# MoogFilter_DIL.net
KiCad netlist of a schematic drawn in EAGLE
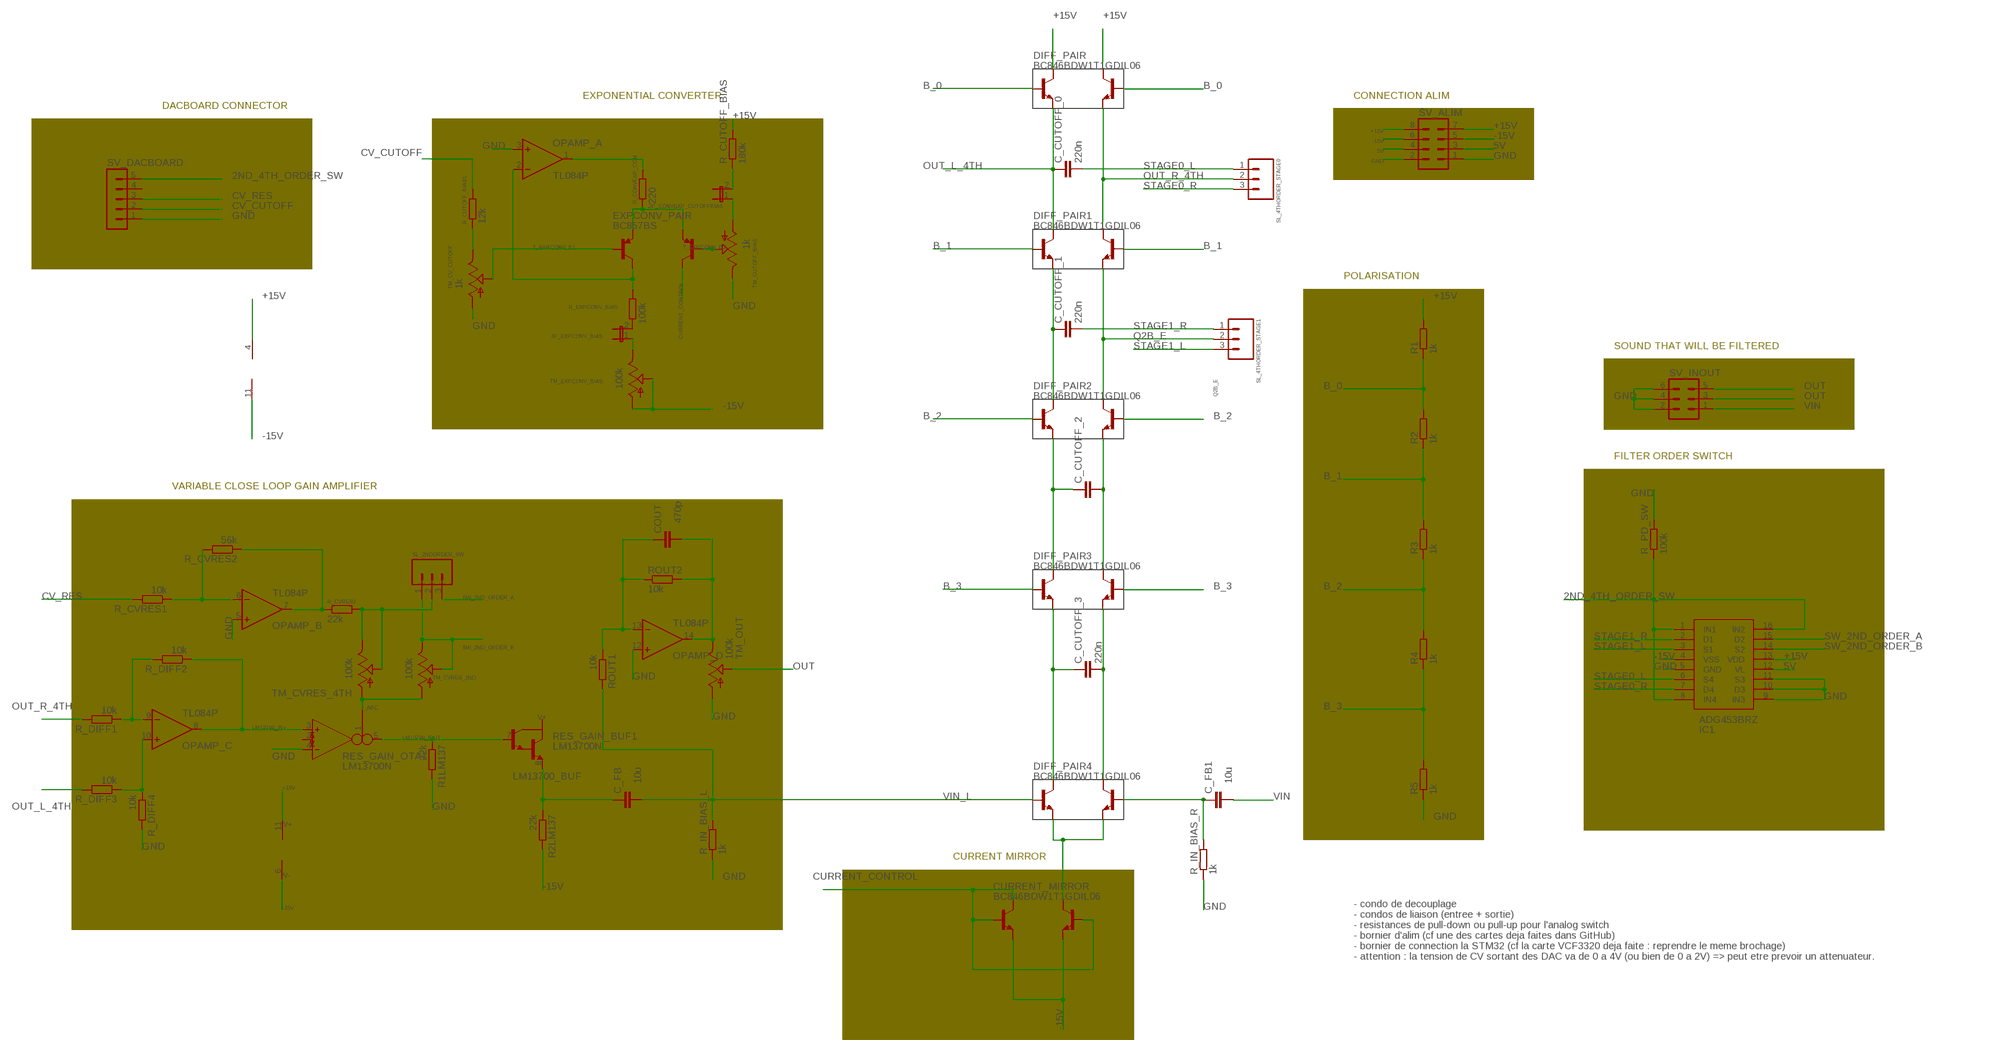
[diagram p0: schematic, sheet 1]

(export (version "E")
  (design (tool "Eeschema 10.0.6"))
  (components
    (comp (ref "COUT")
      (value "470p")
      (footprint "eagle-import:C5B2.5")
      (libsource (lib "eagle-import") (part "C5/2.5"))
    )
    (comp (ref "CURRENT_MIRROR")
      (value "BC846BDW1T1GDIL06")
      (footprint "eagle-import:DIL06")
      (libsource (lib "eagle-import") (part "BC846BDW1T1GDIL06"))
    )
    (comp (ref "C_CUTOFF_0")
      (value "220n")
      (footprint "eagle-import:C5B3")
      (libsource (lib "eagle-import") (part "C5/3"))
    )
    (comp (ref "C_CUTOFF_1")
      (value "220n")
      (footprint "eagle-import:C5B2.5")
      (libsource (lib "eagle-import") (part "C5/2.5"))
    )
    (comp (ref "C_CUTOFF_2")
      (value "220n")
      (footprint "eagle-import:C5B2.5")
      (libsource (lib "eagle-import") (part "C5/2.5"))
    )
    (comp (ref "C_CUTOFF_3")
      (value "220n")
      (footprint "eagle-import:C5B2.5")
      (libsource (lib "eagle-import") (part "C5/2.5"))
    )
    (comp (ref "C_FB")
      (value "10u")
      (footprint "eagle-import:C5B2.5")
      (libsource (lib "eagle-import") (part "C5/2.5"))
    )
    (comp (ref "C_FB1")
      (value "10u")
      (footprint "eagle-import:C5B2.5")
      (libsource (lib "eagle-import") (part "C5/2.5"))
    )
    (comp (ref "DIFF_PAIR")
      (value "BC846BDW1T1GDIL06")
      (footprint "eagle-import:DIL06")
      (libsource (lib "eagle-import") (part "BC846BDW1T1GDIL06"))
    )
    (comp (ref "DIFF_PAIR1")
      (value "BC846BDW1T1GDIL06")
      (footprint "eagle-import:DIL06")
      (libsource (lib "eagle-import") (part "BC846BDW1T1GDIL06"))
    )
    (comp (ref "DIFF_PAIR2")
      (value "BC846BDW1T1GDIL06")
      (footprint "eagle-import:DIL06")
      (libsource (lib "eagle-import") (part "BC846BDW1T1GDIL06"))
    )
    (comp (ref "DIFF_PAIR3")
      (value "BC846BDW1T1GDIL06")
      (footprint "eagle-import:DIL06")
      (libsource (lib "eagle-import") (part "BC846BDW1T1GDIL06"))
    )
    (comp (ref "DIFF_PAIR4")
      (value "BC846BDW1T1GDIL06")
      (footprint "eagle-import:DIL06")
      (libsource (lib "eagle-import") (part "BC846BDW1T1GDIL06"))
    )
    (comp (ref "EXPCONV_PAIR")
      (value "BC857BS")
      (footprint "eagle-import:DIL06")
      (libsource (lib "eagle-import") (part "BC857BS"))
    )
    (comp (ref "IC1")
      (value "ADG453BRZ")
      (footprint "eagle-import:SOIC127P600X175-16N")
      (fields (field (name "MOUSER_PART_NUMBER") "584-ADG453BRZ") (field (name "RS_PART_NUMBER") "0412539P"))
      (libsource (lib "eagle-import") (part "ADG453BRZ"))
    )
    (comp (ref "JP_CONVEXP_CUTOFFBIAS")
      (value "JP1E")
      (footprint "eagle-import:JP1")
      (libsource (lib "eagle-import") (part "JP1E"))
    )
    (comp (ref "JP_EXPCONV_BIAS")
      (value "JP1E")
      (footprint "eagle-import:JP1")
      (libsource (lib "eagle-import") (part "JP1E"))
    )
    (comp (ref "OPAMP_")
      (value "TL084P")
      (footprint "eagle-import:DIL14")
      (libsource (lib "eagle-import") (part "TL084P"))
    )
    (comp (ref "R1")
      (value "1k")
      (footprint "eagle-import:0204_7")
      (libsource (lib "eagle-import") (part "R-EU_0204/7"))
    )
    (comp (ref "R1LM137")
      (value "22k")
      (footprint "eagle-import:0204_7")
      (libsource (lib "eagle-import") (part "R-EU_0204/7"))
    )
    (comp (ref "R2")
      (value "1k")
      (footprint "eagle-import:0204_7")
      (libsource (lib "eagle-import") (part "R-EU_0204/7"))
    )
    (comp (ref "R2LM137")
      (value "22k")
      (footprint "eagle-import:0204_7")
      (libsource (lib "eagle-import") (part "R-EU_0204/7"))
    )
    (comp (ref "R3")
      (value "1k")
      (footprint "eagle-import:0204_7")
      (libsource (lib "eagle-import") (part "R-EU_0204/7"))
    )
    (comp (ref "R4")
      (value "1k")
      (footprint "eagle-import:0204_7")
      (libsource (lib "eagle-import") (part "R-EU_0204/7"))
    )
    (comp (ref "R5")
      (value "1k")
      (footprint "eagle-import:0204_7")
      (libsource (lib "eagle-import") (part "R-EU_0204/7"))
    )
    (comp (ref "RES_GAIN_")
      (value "LM13700N")
      (footprint "eagle-import:DIL16")
      (libsource (lib "eagle-import") (part "LM13700N"))
    )
    (comp (ref "ROUT1")
      (value "10k")
      (footprint "eagle-import:0204_7")
      (libsource (lib "eagle-import") (part "R-EU_0204/7"))
    )
    (comp (ref "ROUT2")
      (value "10k")
      (footprint "eagle-import:0204_7")
      (libsource (lib "eagle-import") (part "R-EU_0204/7"))
    )
    (comp (ref "R_CONVEXP_COM")
      (value "220")
      (footprint "eagle-import:0204_7")
      (libsource (lib "eagle-import") (part "R-EU_0204/7"))
    )
    (comp (ref "R_CUTOFF_BIAS")
      (value "180k")
      (footprint "eagle-import:0204_7")
      (libsource (lib "eagle-import") (part "R-EU_0204/7"))
    )
    (comp (ref "R_CUTOFF_BIAS1")
      (value "12k")
      (footprint "eagle-import:0204_7")
      (libsource (lib "eagle-import") (part "R-EU_0204/7"))
    )
    (comp (ref "R_CVRES1")
      (value "10k")
      (footprint "eagle-import:0204_7")
      (libsource (lib "eagle-import") (part "R-EU_0204/7"))
    )
    (comp (ref "R_CVRES2")
      (value "56k")
      (footprint "eagle-import:0204_7")
      (libsource (lib "eagle-import") (part "R-EU_0204/7"))
    )
    (comp (ref "R_CVRES3")
      (value "22k")
      (footprint "eagle-import:0204_7")
      (libsource (lib "eagle-import") (part "R-EU_0204/7"))
    )
    (comp (ref "R_DIFF1")
      (value "10k")
      (footprint "eagle-import:0204_7")
      (libsource (lib "eagle-import") (part "R-EU_0204/7"))
    )
    (comp (ref "R_DIFF2")
      (value "10k")
      (footprint "eagle-import:0204_7")
      (libsource (lib "eagle-import") (part "R-EU_0204/7"))
    )
    (comp (ref "R_DIFF3")
      (value "10k")
      (footprint "eagle-import:0204_7")
      (libsource (lib "eagle-import") (part "R-EU_0204/7"))
    )
    (comp (ref "R_DIFF4")
      (value "10k")
      (footprint "eagle-import:0204_7")
      (libsource (lib "eagle-import") (part "R-EU_0204/7"))
    )
    (comp (ref "R_EXPCONV_BIAS")
      (value "100k")
      (footprint "eagle-import:0204_7")
      (libsource (lib "eagle-import") (part "R-EU_0204/7"))
    )
    (comp (ref "R_IN_BIAS_L")
      (value "1k")
      (footprint "eagle-import:0204_7")
      (libsource (lib "eagle-import") (part "R-EU_0204/7"))
    )
    (comp (ref "R_IN_BIAS_R")
      (value "1k")
      (footprint "eagle-import:0204_7")
      (libsource (lib "eagle-import") (part "R-EU_0204/7"))
    )
    (comp (ref "R_PD_SW")
      (value "100k")
      (footprint "eagle-import:0204_7")
      (libsource (lib "eagle-import") (part "R-EU_0204/7"))
    )
    (comp (ref "SL_2NDORDER_SW")
      (value "MA03")
      (footprint "eagle-import:03P")
      (libsource (lib "eagle-import") (part "MA03"))
    )
    (comp (ref "SL_4THORDER_STAGE0")
      (value "MA03")
      (footprint "eagle-import:03P")
      (libsource (lib "eagle-import") (part "MA03"))
    )
    (comp (ref "SL_4THORDER_STAGE1")
      (value "MA03")
      (footprint "eagle-import:03P")
      (libsource (lib "eagle-import") (part "MA03"))
    )
    (comp (ref "SV_ALIM")
      (value "MA04-2")
      (footprint "eagle-import:MA04-2")
      (libsource (lib "eagle-import") (part "MA04-2"))
    )
    (comp (ref "SV_DACBOARD")
      (value "MA05-1")
      (footprint "eagle-import:MA05-1")
      (libsource (lib "eagle-import") (part "MA05-1"))
    )
    (comp (ref "SV_INOUT")
      (value "MA03-2")
      (footprint "eagle-import:MA03-2")
      (libsource (lib "eagle-import") (part "MA03-2"))
    )
    (comp (ref "TM_CUTOFF_BIAS")
      (value "1k")
      (footprint "eagle-import:6MM")
      (libsource (lib "eagle-import") (part "TRIM"))
    )
    (comp (ref "TM_CVRES_2ND")
      (value "100k")
      (footprint "eagle-import:6MM")
      (libsource (lib "eagle-import") (part "TRIM"))
    )
    (comp (ref "TM_CVRES_4TH")
      (value "100k")
      (footprint "eagle-import:6MM")
      (libsource (lib "eagle-import") (part "TRIM"))
    )
    (comp (ref "TM_CV_CUTOFF")
      (value "1k")
      (footprint "eagle-import:6MM")
      (libsource (lib "eagle-import") (part "TRIM"))
    )
    (comp (ref "TM_EXPCONV_BIAS")
      (value "100k")
      (footprint "eagle-import:6MM")
      (libsource (lib "eagle-import") (part "TRIM"))
    )
    (comp (ref "TM_OUT")
      (value "100k")
      (footprint "eagle-import:6MM")
      (libsource (lib "eagle-import") (part "TRIM"))
    )
  )
  (nets
    (net (code "1") (name "/+15V") (class "Default")
      (node (ref "DIFF_PAIR") (pin "3") (pinfunction "C1_3") (pintype "passive"))
      (node (ref "DIFF_PAIR") (pin "6") (pinfunction "C2_6") (pintype "passive"))
      (node (ref "IC1") (pin "13") (pinfunction "VDD_13") (pintype "bidirectional"))
      (node (ref "OPAMP_") (pin "4") (pinfunction "V+_4") (pintype "power_in"))
      (node (ref "R1") (pin "2") (pinfunction "2_2") (pintype "passive"))
      (node (ref "RES_GAIN_") (pin "11") (pinfunction "V+_11") (pintype "power_in"))
      (node (ref "R_CUTOFF_BIAS") (pin "2") (pinfunction "2_2") (pintype "passive"))
      (node (ref "SV_ALIM") (pin "7") (pinfunction "7_7") (pintype "passive"))
      (node (ref "SV_ALIM") (pin "8") (pinfunction "8_8") (pintype "passive"))
    )
    (net (code "2") (name "/-15V") (class "Default")
      (node (ref "CURRENT_MIRROR") (pin "1") (pinfunction "E2_1") (pintype "passive"))
      (node (ref "CURRENT_MIRROR") (pin "4") (pinfunction "E1_4") (pintype "passive"))
      (node (ref "IC1") (pin "4") (pinfunction "VSS_4") (pintype "bidirectional"))
      (node (ref "OPAMP_") (pin "11") (pinfunction "V-_11") (pintype "power_in"))
      (node (ref "R2LM137") (pin "2") (pinfunction "2_2") (pintype "passive"))
      (node (ref "RES_GAIN_") (pin "6") (pinfunction "V-_6") (pintype "power_in"))
      (node (ref "SV_ALIM") (pin "5") (pinfunction "5_5") (pintype "passive"))
      (node (ref "SV_ALIM") (pin "6") (pinfunction "6_6") (pintype "passive"))
      (node (ref "TM_EXPCONV_BIAS") (pin "A") (pinfunction "A_A") (pintype "passive"))
      (node (ref "TM_EXPCONV_BIAS") (pin "S") (pinfunction "S_S") (pintype "passive"))
    )
    (net (code "3") (name "/2ND_4TH_ORDER_SW") (class "Default")
      (node (ref "IC1") (pin "1") (pinfunction "IN1_1") (pintype "bidirectional"))
      (node (ref "IC1") (pin "16") (pinfunction "IN2_16") (pintype "bidirectional"))
      (node (ref "IC1") (pin "8") (pinfunction "IN4_8") (pintype "bidirectional"))
      (node (ref "R_PD_SW") (pin "1") (pinfunction "1_1") (pintype "passive"))
      (node (ref "SV_DACBOARD") (pin "5") (pinfunction "5_5") (pintype "passive"))
    )
    (net (code "4") (name "/5V") (class "Default")
      (node (ref "IC1") (pin "12") (pinfunction "VL_12") (pintype "bidirectional"))
      (node (ref "SV_ALIM") (pin "3") (pinfunction "3_3") (pintype "passive"))
      (node (ref "SV_ALIM") (pin "4") (pinfunction "4_4") (pintype "passive"))
    )
    (net (code "5") (name "/B_0") (class "Default")
      (node (ref "DIFF_PAIR") (pin "2") (pinfunction "B2_2") (pintype "passive"))
      (node (ref "DIFF_PAIR") (pin "5") (pinfunction "B1_5") (pintype "passive"))
      (node (ref "R1") (pin "1") (pinfunction "1_1") (pintype "passive"))
      (node (ref "R2") (pin "2") (pinfunction "2_2") (pintype "passive"))
    )
    (net (code "6") (name "/B_1") (class "Default")
      (node (ref "DIFF_PAIR1") (pin "2") (pinfunction "B2_2") (pintype "passive"))
      (node (ref "DIFF_PAIR1") (pin "5") (pinfunction "B1_5") (pintype "passive"))
      (node (ref "R2") (pin "1") (pinfunction "1_1") (pintype "passive"))
      (node (ref "R3") (pin "2") (pinfunction "2_2") (pintype "passive"))
    )
    (net (code "7") (name "/B_2") (class "Default")
      (node (ref "DIFF_PAIR2") (pin "2") (pinfunction "B2_2") (pintype "passive"))
      (node (ref "DIFF_PAIR2") (pin "5") (pinfunction "B1_5") (pintype "passive"))
      (node (ref "R3") (pin "1") (pinfunction "1_1") (pintype "passive"))
      (node (ref "R4") (pin "2") (pinfunction "2_2") (pintype "passive"))
    )
    (net (code "8") (name "/B_3") (class "Default")
      (node (ref "DIFF_PAIR3") (pin "2") (pinfunction "B2_2") (pintype "passive"))
      (node (ref "DIFF_PAIR3") (pin "5") (pinfunction "B1_5") (pintype "passive"))
      (node (ref "R4") (pin "1") (pinfunction "1_1") (pintype "passive"))
      (node (ref "R5") (pin "2") (pinfunction "2_2") (pintype "passive"))
    )
    (net (code "9") (name "/CURRENT_CONTROL") (class "Default")
      (node (ref "CURRENT_MIRROR") (pin "2") (pinfunction "B2_2") (pintype "passive"))
      (node (ref "CURRENT_MIRROR") (pin "3") (pinfunction "C1_3") (pintype "passive"))
      (node (ref "CURRENT_MIRROR") (pin "5") (pinfunction "B1_5") (pintype "passive"))
      (node (ref "EXPCONV_PAIR") (pin "3") (pinfunction "C2_3") (pintype "passive"))
    )
    (net (code "10") (name "/CV_CUTOFF") (class "Default")
      (node (ref "R_CUTOFF_BIAS1") (pin "2") (pinfunction "2_2") (pintype "passive"))
      (node (ref "SV_DACBOARD") (pin "2") (pinfunction "2_2") (pintype "passive"))
    )
    (net (code "11") (name "/CV_RES") (class "Default")
      (node (ref "R_CVRES1") (pin "2") (pinfunction "2_2") (pintype "passive"))
      (node (ref "SV_DACBOARD") (pin "3") (pinfunction "3_3") (pintype "passive"))
    )
    (net (code "12") (name "/GND") (class "Default")
      (node (ref "IC1") (pin "10") (pinfunction "D3_10") (pintype "bidirectional"))
      (node (ref "IC1") (pin "11") (pinfunction "S3_11") (pintype "bidirectional"))
      (node (ref "IC1") (pin "5") (pinfunction "GND_5") (pintype "bidirectional"))
      (node (ref "IC1") (pin "9") (pinfunction "IN3_9") (pintype "bidirectional"))
      (node (ref "OPAMP_") (pin "12") (pinfunction "+IN_12") (pintype "input"))
      (node (ref "OPAMP_") (pin "3") (pinfunction "+IN_3") (pintype "input"))
      (node (ref "OPAMP_") (pin "5") (pinfunction "+IN_5") (pintype "input"))
      (node (ref "R1LM137") (pin "2") (pinfunction "2_2") (pintype "passive"))
      (node (ref "R5") (pin "1") (pinfunction "1_1") (pintype "passive"))
      (node (ref "RES_GAIN_") (pin "4") (pinfunction "IN_N_4") (pintype "input"))
      (node (ref "R_DIFF4") (pin "2") (pinfunction "2_2") (pintype "passive"))
      (node (ref "R_IN_BIAS_L") (pin "1") (pinfunction "1_1") (pintype "passive"))
      (node (ref "R_IN_BIAS_R") (pin "1") (pinfunction "1_1") (pintype "passive"))
      (node (ref "R_PD_SW") (pin "2") (pinfunction "2_2") (pintype "passive"))
      (node (ref "SV_ALIM") (pin "1") (pinfunction "1_1") (pintype "passive"))
      (node (ref "SV_ALIM") (pin "2") (pinfunction "2_2") (pintype "passive"))
      (node (ref "SV_DACBOARD") (pin "1") (pinfunction "1_1") (pintype "passive"))
      (node (ref "SV_INOUT") (pin "2") (pinfunction "2_2") (pintype "passive"))
      (node (ref "SV_INOUT") (pin "4") (pinfunction "4_4") (pintype "passive"))
      (node (ref "SV_INOUT") (pin "6") (pinfunction "6_6") (pintype "passive"))
      (node (ref "TM_CUTOFF_BIAS") (pin "E") (pinfunction "E_E") (pintype "passive"))
      (node (ref "TM_CV_CUTOFF") (pin "A") (pinfunction "A_A") (pintype "passive"))
      (node (ref "TM_OUT") (pin "A") (pinfunction "A_A") (pintype "passive"))
    )
    (net (code "13") (name "/I_ABC") (class "Default")
      (node (ref "RES_GAIN_") (pin "1") (pinfunction "I_BIAS_1") (pintype "input"))
      (node (ref "TM_CVRES_2ND") (pin "A") (pinfunction "A_A") (pintype "passive"))
      (node (ref "TM_CVRES_4TH") (pin "A") (pinfunction "A_A") (pintype "passive"))
    )
    (net (code "14") (name "/LM13700_BUF") (class "Default")
      (node (ref "C_FB") (pin "1") (pinfunction "1_1") (pintype "passive"))
      (node (ref "R2LM137") (pin "1") (pinfunction "1_1") (pintype "passive"))
      (node (ref "RES_GAIN_") (pin "8") (pinfunction "E_8") (pintype "passive"))
    )
    (net (code "15") (name "/LM13700_IN+") (class "Default")
      (node (ref "OPAMP_") (pin "8") (pinfunction "OUT_8") (pintype "output"))
      (node (ref "RES_GAIN_") (pin "3") (pinfunction "IN_P_3") (pintype "input"))
      (node (ref "R_DIFF2") (pin "1") (pinfunction "1_1") (pintype "passive"))
    )
    (net (code "16") (name "/LM13700_IOUT") (class "Default")
      (node (ref "R1LM137") (pin "1") (pinfunction "1_1") (pintype "passive"))
      (node (ref "RES_GAIN_") (pin "5") (pinfunction "OUT_5") (pintype "output"))
      (node (ref "RES_GAIN_") (pin "7") (pinfunction "B_7") (pintype "passive"))
    )
    (net (code "17") (name "/OUT") (class "Default")
      (node (ref "SV_INOUT") (pin "3") (pinfunction "3_3") (pintype "passive"))
      (node (ref "SV_INOUT") (pin "5") (pinfunction "5_5") (pintype "passive"))
      (node (ref "TM_OUT") (pin "S") (pinfunction "S_S") (pintype "passive"))
    )
    (net (code "18") (name "/OUT_L_4TH") (class "Default")
      (node (ref "C_CUTOFF_0") (pin "1") (pinfunction "1_1") (pintype "passive"))
      (node (ref "DIFF_PAIR") (pin "4") (pinfunction "E1_4") (pintype "passive"))
      (node (ref "DIFF_PAIR1") (pin "3") (pinfunction "C1_3") (pintype "passive"))
      (node (ref "R_DIFF3") (pin "2") (pinfunction "2_2") (pintype "passive"))
    )
    (net (code "19") (name "/OUT_R_4TH") (class "Default")
      (node (ref "DIFF_PAIR") (pin "1") (pinfunction "E2_1") (pintype "passive"))
      (node (ref "DIFF_PAIR1") (pin "6") (pinfunction "C2_6") (pintype "passive"))
      (node (ref "R_DIFF1") (pin "2") (pinfunction "2_2") (pintype "passive"))
      (node (ref "SL_4THORDER_STAGE0") (pin "2") (pinfunction "2_2") (pintype "passive"))
    )
    (net (code "20") (name "/Q2B_E") (class "Default")
      (node (ref "DIFF_PAIR1") (pin "1") (pinfunction "E2_1") (pintype "passive"))
      (node (ref "DIFF_PAIR2") (pin "6") (pinfunction "C2_6") (pintype "passive"))
      (node (ref "SL_4THORDER_STAGE1") (pin "2") (pinfunction "2_2") (pintype "passive"))
    )
    (net (code "21") (name "/STAGE0_L") (class "Default")
      (node (ref "C_CUTOFF_0") (pin "2") (pinfunction "2_2") (pintype "passive"))
      (node (ref "IC1") (pin "6") (pinfunction "S4_6") (pintype "bidirectional"))
      (node (ref "SL_4THORDER_STAGE0") (pin "1") (pinfunction "1_1") (pintype "passive"))
    )
    (net (code "22") (name "/STAGE0_R") (class "Default")
      (node (ref "IC1") (pin "7") (pinfunction "D4_7") (pintype "bidirectional"))
      (node (ref "SL_4THORDER_STAGE0") (pin "3") (pinfunction "3_3") (pintype "passive"))
    )
    (net (code "23") (name "/STAGE1_L") (class "Default")
      (node (ref "IC1") (pin "3") (pinfunction "S1_3") (pintype "bidirectional"))
      (node (ref "SL_4THORDER_STAGE1") (pin "3") (pinfunction "3_3") (pintype "passive"))
    )
    (net (code "24") (name "/STAGE1_R") (class "Default")
      (node (ref "C_CUTOFF_1") (pin "2") (pinfunction "2_2") (pintype "passive"))
      (node (ref "IC1") (pin "2") (pinfunction "D1_2") (pintype "bidirectional"))
      (node (ref "SL_4THORDER_STAGE1") (pin "1") (pinfunction "1_1") (pintype "passive"))
    )
    (net (code "25") (name "/SW_2ND_ORDER_A") (class "Default")
      (node (ref "IC1") (pin "15") (pinfunction "D2_15") (pintype "bidirectional"))
      (node (ref "SL_2NDORDER_SW") (pin "3") (pinfunction "3_3") (pintype "passive"))
    )
    (net (code "26") (name "/SW_2ND_ORDER_B") (class "Default")
      (node (ref "IC1") (pin "14") (pinfunction "S2_14") (pintype "bidirectional"))
      (node (ref "SL_2NDORDER_SW") (pin "1") (pinfunction "1_1") (pintype "passive"))
      (node (ref "TM_CVRES_2ND") (pin "E") (pinfunction "E_E") (pintype "passive"))
      (node (ref "TM_CVRES_2ND") (pin "S") (pinfunction "S_S") (pintype "passive"))
    )
    (net (code "27") (name "/T_EXPCONV_B1") (class "Default")
      (node (ref "EXPCONV_PAIR") (pin "2") (pinfunction "B1_2") (pintype "passive"))
      (node (ref "TM_CV_CUTOFF") (pin "S") (pinfunction "S_S") (pintype "passive"))
    )
    (net (code "28") (name "/T_EXPCONV_B2") (class "Default")
      (node (ref "EXPCONV_PAIR") (pin "5") (pinfunction "B2_5") (pintype "passive"))
      (node (ref "TM_CUTOFF_BIAS") (pin "S") (pinfunction "S_S") (pintype "passive"))
    )
    (net (code "29") (name "/VIN") (class "Default")
      (node (ref "C_FB1") (pin "2") (pinfunction "2_2") (pintype "passive"))
      (node (ref "SV_INOUT") (pin "1") (pinfunction "1_1") (pintype "passive"))
    )
    (net (code "30") (name "/VIN_L") (class "Default")
      (node (ref "C_FB") (pin "2") (pinfunction "2_2") (pintype "passive"))
      (node (ref "DIFF_PAIR4") (pin "5") (pinfunction "B1_5") (pintype "passive"))
      (node (ref "ROUT1") (pin "2") (pinfunction "2_2") (pintype "passive"))
      (node (ref "R_IN_BIAS_L") (pin "2") (pinfunction "2_2") (pintype "passive"))
    )
    (net (code "31") (name "Net-(CURRENT_MIRROR-C2)") (class "Default")
      (node (ref "CURRENT_MIRROR") (pin "6") (pinfunction "C2_6") (pintype "passive"))
      (node (ref "DIFF_PAIR4") (pin "1") (pinfunction "E2_1") (pintype "passive"))
      (node (ref "DIFF_PAIR4") (pin "4") (pinfunction "E1_4") (pintype "passive"))
    )
    (net (code "32") (name "Net-(DIFF_PAIR1-E1)") (class "Default")
      (node (ref "C_CUTOFF_1") (pin "1") (pinfunction "1_1") (pintype "passive"))
      (node (ref "DIFF_PAIR1") (pin "4") (pinfunction "E1_4") (pintype "passive"))
      (node (ref "DIFF_PAIR2") (pin "3") (pinfunction "C1_3") (pintype "passive"))
    )
    (net (code "33") (name "Net-(DIFF_PAIR2-E1)") (class "Default")
      (node (ref "C_CUTOFF_2") (pin "1") (pinfunction "1_1") (pintype "passive"))
      (node (ref "DIFF_PAIR2") (pin "4") (pinfunction "E1_4") (pintype "passive"))
      (node (ref "DIFF_PAIR3") (pin "3") (pinfunction "C1_3") (pintype "passive"))
    )
    (net (code "34") (name "Net-(DIFF_PAIR2-E2)") (class "Default")
      (node (ref "C_CUTOFF_2") (pin "2") (pinfunction "2_2") (pintype "passive"))
      (node (ref "DIFF_PAIR2") (pin "1") (pinfunction "E2_1") (pintype "passive"))
      (node (ref "DIFF_PAIR3") (pin "6") (pinfunction "C2_6") (pintype "passive"))
    )
    (net (code "35") (name "Net-(DIFF_PAIR3-E1)") (class "Default")
      (node (ref "C_CUTOFF_3") (pin "1") (pinfunction "1_1") (pintype "passive"))
      (node (ref "DIFF_PAIR3") (pin "4") (pinfunction "E1_4") (pintype "passive"))
      (node (ref "DIFF_PAIR4") (pin "3") (pinfunction "C1_3") (pintype "passive"))
    )
    (net (code "36") (name "Net-(DIFF_PAIR3-E2)") (class "Default")
      (node (ref "C_CUTOFF_3") (pin "2") (pinfunction "2_2") (pintype "passive"))
      (node (ref "DIFF_PAIR3") (pin "1") (pinfunction "E2_1") (pintype "passive"))
      (node (ref "DIFF_PAIR4") (pin "6") (pinfunction "C2_6") (pintype "passive"))
    )
    (net (code "37") (name "Net-(DIFF_PAIR4-B2)") (class "Default")
      (node (ref "C_FB1") (pin "1") (pinfunction "1_1") (pintype "passive"))
      (node (ref "DIFF_PAIR4") (pin "2") (pinfunction "B2_2") (pintype "passive"))
      (node (ref "R_IN_BIAS_R") (pin "2") (pinfunction "2_2") (pintype "passive"))
    )
    (net (code "38") (name "Net-(EXPCONV_PAIR-C1)") (class "Default")
      (node (ref "EXPCONV_PAIR") (pin "6") (pinfunction "C1_6") (pintype "passive"))
      (node (ref "OPAMP_") (pin "2") (pinfunction "-IN_2") (pintype "input"))
      (node (ref "R_EXPCONV_BIAS") (pin "2") (pinfunction "2_2") (pintype "passive"))
    )
    (net (code "39") (name "Net-(EXPCONV_PAIR-E1)") (class "Default")
      (node (ref "EXPCONV_PAIR") (pin "1") (pinfunction "E1_1") (pintype "passive"))
      (node (ref "EXPCONV_PAIR") (pin "4") (pinfunction "E2_4") (pintype "passive"))
      (node (ref "R_CONVEXP_COM") (pin "1") (pinfunction "1_1") (pintype "passive"))
    )
    (net (code "40") (name "Net-(JP_CONVEXP_CUTOFFBIAS-Pad1)") (class "Default")
      (node (ref "JP_CONVEXP_CUTOFFBIAS") (pin "1") (pinfunction "1_1") (pintype "passive"))
      (node (ref "TM_CUTOFF_BIAS") (pin "A") (pinfunction "A_A") (pintype "passive"))
    )
    (net (code "41") (name "Net-(JP_CONVEXP_CUTOFFBIAS-Pad2)") (class "Default")
      (node (ref "JP_CONVEXP_CUTOFFBIAS") (pin "2") (pinfunction "2_2") (pintype "passive"))
      (node (ref "R_CUTOFF_BIAS") (pin "1") (pinfunction "1_1") (pintype "passive"))
    )
    (net (code "42") (name "Net-(JP_EXPCONV_BIAS-Pad1)") (class "Default")
      (node (ref "JP_EXPCONV_BIAS") (pin "1") (pinfunction "1_1") (pintype "passive"))
      (node (ref "TM_EXPCONV_BIAS") (pin "E") (pinfunction "E_E") (pintype "passive"))
    )
    (net (code "43") (name "Net-(JP_EXPCONV_BIAS-Pad2)") (class "Default")
      (node (ref "JP_EXPCONV_BIAS") (pin "2") (pinfunction "2_2") (pintype "passive"))
      (node (ref "R_EXPCONV_BIAS") (pin "1") (pinfunction "1_1") (pintype "passive"))
    )
    (net (code "44") (name "Net-(OPAMP_A-OUT)") (class "Default")
      (node (ref "OPAMP_") (pin "1") (pinfunction "OUT_1") (pintype "output"))
      (node (ref "R_CONVEXP_COM") (pin "2") (pinfunction "2_2") (pintype "passive"))
    )
    (net (code "45") (name "Net-(OPAMP_B--IN)") (class "Default")
      (node (ref "OPAMP_") (pin "6") (pinfunction "-IN_6") (pintype "input"))
      (node (ref "R_CVRES1") (pin "1") (pinfunction "1_1") (pintype "passive"))
      (node (ref "R_CVRES2") (pin "2") (pinfunction "2_2") (pintype "passive"))
    )
    (net (code "46") (name "Net-(OPAMP_B-OUT)") (class "Default")
      (node (ref "OPAMP_") (pin "7") (pinfunction "OUT_7") (pintype "output"))
      (node (ref "R_CVRES2") (pin "1") (pinfunction "1_1") (pintype "passive"))
      (node (ref "R_CVRES3") (pin "1") (pinfunction "1_1") (pintype "passive"))
    )
    (net (code "47") (name "Net-(OPAMP_C-+IN)") (class "Default")
      (node (ref "OPAMP_") (pin "10") (pinfunction "+IN_10") (pintype "input"))
      (node (ref "R_DIFF3") (pin "1") (pinfunction "1_1") (pintype "passive"))
      (node (ref "R_DIFF4") (pin "1") (pinfunction "1_1") (pintype "passive"))
    )
    (net (code "48") (name "Net-(OPAMP_C--IN)") (class "Default")
      (node (ref "OPAMP_") (pin "9") (pinfunction "-IN_9") (pintype "input"))
      (node (ref "R_DIFF1") (pin "1") (pinfunction "1_1") (pintype "passive"))
      (node (ref "R_DIFF2") (pin "2") (pinfunction "2_2") (pintype "passive"))
    )
    (net (code "49") (name "Net-(OPAMP_D--IN)") (class "Default")
      (node (ref "COUT") (pin "1") (pinfunction "1_1") (pintype "passive"))
      (node (ref "OPAMP_") (pin "13") (pinfunction "-IN_13") (pintype "input"))
      (node (ref "ROUT1") (pin "1") (pinfunction "1_1") (pintype "passive"))
      (node (ref "ROUT2") (pin "1") (pinfunction "1_1") (pintype "passive"))
    )
    (net (code "50") (name "Net-(OPAMP_D-OUT)") (class "Default")
      (node (ref "COUT") (pin "2") (pinfunction "2_2") (pintype "passive"))
      (node (ref "OPAMP_") (pin "14") (pinfunction "OUT_14") (pintype "output"))
      (node (ref "ROUT2") (pin "2") (pinfunction "2_2") (pintype "passive"))
      (node (ref "TM_OUT") (pin "E") (pinfunction "E_E") (pintype "passive"))
    )
    (net (code "51") (name "Net-(R_CUTOFF_BIAS1-Pad1)") (class "Default")
      (node (ref "R_CUTOFF_BIAS1") (pin "1") (pinfunction "1_1") (pintype "passive"))
      (node (ref "TM_CV_CUTOFF") (pin "E") (pinfunction "E_E") (pintype "passive"))
    )
    (net (code "52") (name "Net-(R_CVRES3-Pad2)") (class "Default")
      (node (ref "R_CVRES3") (pin "2") (pinfunction "2_2") (pintype "passive"))
      (node (ref "SL_2NDORDER_SW") (pin "2") (pinfunction "2_2") (pintype "passive"))
      (node (ref "TM_CVRES_4TH") (pin "E") (pinfunction "E_E") (pintype "passive"))
      (node (ref "TM_CVRES_4TH") (pin "S") (pinfunction "S_S") (pintype "passive"))
    )
    (net (code "53") (name "unconnected-(RES_GAIN_C-I_DIODE-Pad2)") (class "Default")
      (node (ref "RES_GAIN_") (pin "2") (pinfunction "I_DIODE_2") (pintype "input"))
    )
    (net (code "54") (name "unconnected-(SV_DACBOARD-Pad4)") (class "Default")
      (node (ref "SV_DACBOARD") (pin "4") (pinfunction "4_4") (pintype "passive"))
    )
  )
)
